# user.net
KiCad netlist of a schematic drawn in Altium Designer
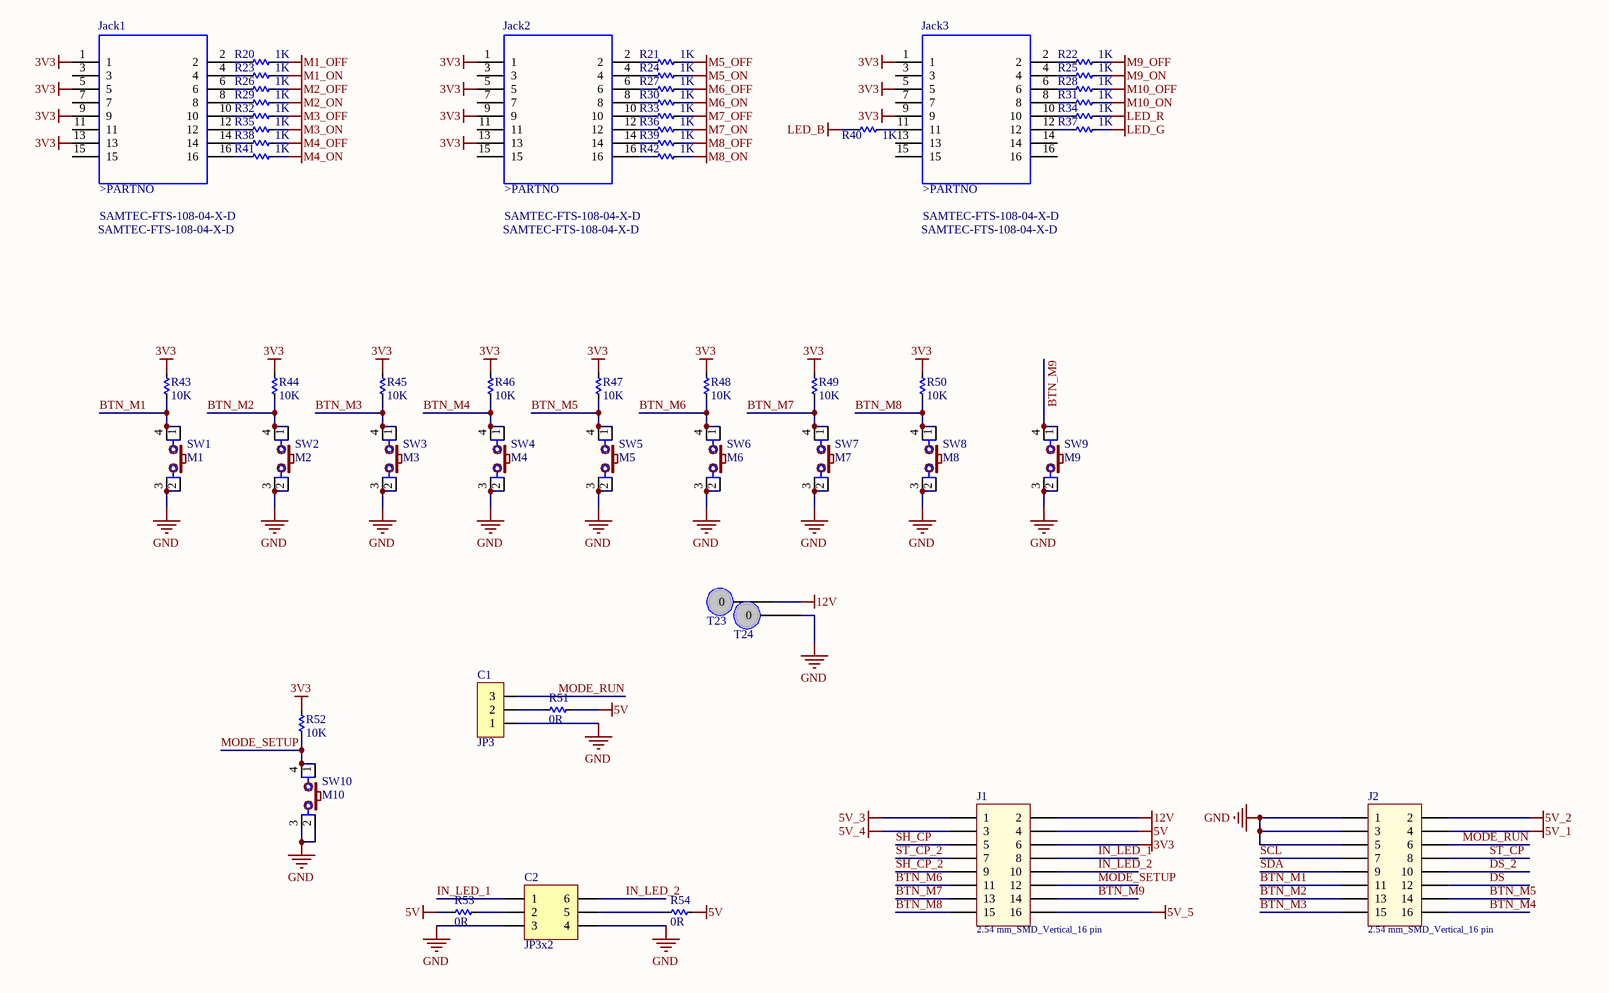
[diagram p0: user.SchDoc]

(export (version "E")
  (design (tool "Eeschema 10.0.6"))
  (components
    (comp (ref "C1")
      (value "JP3")
      (footprint "JP3-D1C")
      (description "WR-PHD 2.54 mm Angled Socket Header")
      (fields
        (field (name "MANUFACTURER") "Würth Elektronik eiSos GmbH")
        (field (name "PARTNO") "613003143121")
        (field (name "CREATED BY") "Karrer Zheng")
      )
      (libsource (lib "LIBRARY") (part "JP3"))
    )
    (comp (ref "C2")
      (value "JP3x2")
      (footprint "JP3-D2C")
      (description "WR-PHD 2.54 mm Dual Socket Header")
      (fields
        (field (name "MANUFACTURER") "Würth Elektronik eiSos GmbH")
        (field (name "PARTNO") "61300621821")
        (field (name "CREATED BY") "Karrer Zheng")
      )
      (libsource (lib "LIBRARY") (part "JP3x2"))
    )
    (comp (ref "J1")
      (value "2.54 mm_SMD_Vertical_16 pin")
      (footprint "61031621121")
      (description "Pin Header WR-PHD, pitch 2.54 mm, SMD, Vertical, dual row, 16 pin")
      (fields (field (name "PART NUMBER") "61031621121") (field (name "PUBLISHER") "Wurth Elektronik"))
      (libsource (lib "Jump2.0") (part "61031621121"))
    )
    (comp (ref "J2")
      (value "2.54 mm_SMD_Vertical_16 pin")
      (footprint "61031621121")
      (description "Pin Header WR-PHD, pitch 2.54 mm, SMD, Vertical, dual row, 16 pin")
      (fields (field (name "PART NUMBER") "61031621121") (field (name "PUBLISHER") "Wurth Elektronik"))
      (libsource (lib "Jump2.0") (part "61031621121"))
    )
    (comp (ref "Jack1")
      (value "SAMTEC-FTS-108-04-X-D")
      (footprint "SAMTEC-FTS-108-04-X-D:SAMTEC-FTS-108-04-X-D")
      (libsource (lib "SAMTEC-FTS-108-04-X-D") (part "SAMTEC-FTS-108-04-X-D"))
    )
    (comp (ref "Jack2")
      (value "SAMTEC-FTS-108-04-X-D")
      (footprint "SAMTEC-FTS-108-04-X-D:SAMTEC-FTS-108-04-X-D")
      (libsource (lib "SAMTEC-FTS-108-04-X-D") (part "SAMTEC-FTS-108-04-X-D"))
    )
    (comp (ref "Jack3")
      (value "SAMTEC-FTS-108-04-X-D")
      (footprint "SAMTEC-FTS-108-04-X-D:SAMTEC-FTS-108-04-X-D")
      (libsource (lib "SAMTEC-FTS-108-04-X-D") (part "SAMTEC-FTS-108-04-X-D"))
    )
    (comp (ref "R20")
      (value "1K")
      (footprint "RES-SMD-0603")
      (description "Resistor")
      (fields
        (field (name "MANUFACTURER") "Generic Components")
        (field (name "PUBLISHER") "Altium Hobart Technology Centre")
      )
      (libsource (lib "LIBRARY") (part "Res-SMD"))
    )
    (comp (ref "R21")
      (value "1K")
      (footprint "RES-SMD-0603")
      (description "Resistor")
      (fields
        (field (name "MANUFACTURER") "Generic Components")
        (field (name "PUBLISHER") "Altium Hobart Technology Centre")
      )
      (libsource (lib "LIBRARY") (part "Res-SMD"))
    )
    (comp (ref "R22")
      (value "1K")
      (footprint "RES-SMD-0603")
      (description "Resistor")
      (fields
        (field (name "MANUFACTURER") "Generic Components")
        (field (name "PUBLISHER") "Altium Hobart Technology Centre")
      )
      (libsource (lib "LIBRARY") (part "Res-SMD"))
    )
    (comp (ref "R23")
      (value "1K")
      (footprint "RES-SMD-0603")
      (description "Resistor")
      (fields
        (field (name "MANUFACTURER") "Generic Components")
        (field (name "PUBLISHER") "Altium Hobart Technology Centre")
      )
      (libsource (lib "LIBRARY") (part "Res-SMD"))
    )
    (comp (ref "R24")
      (value "1K")
      (footprint "RES-SMD-0603")
      (description "Resistor")
      (fields
        (field (name "MANUFACTURER") "Generic Components")
        (field (name "PUBLISHER") "Altium Hobart Technology Centre")
      )
      (libsource (lib "LIBRARY") (part "Res-SMD"))
    )
    (comp (ref "R25")
      (value "1K")
      (footprint "RES-SMD-0603")
      (description "Resistor")
      (fields
        (field (name "MANUFACTURER") "Generic Components")
        (field (name "PUBLISHER") "Altium Hobart Technology Centre")
      )
      (libsource (lib "LIBRARY") (part "Res-SMD"))
    )
    (comp (ref "R26")
      (value "1K")
      (footprint "RES-SMD-0603")
      (description "Resistor")
      (fields
        (field (name "MANUFACTURER") "Generic Components")
        (field (name "PUBLISHER") "Altium Hobart Technology Centre")
      )
      (libsource (lib "LIBRARY") (part "Res-SMD"))
    )
    (comp (ref "R27")
      (value "1K")
      (footprint "RES-SMD-0603")
      (description "Resistor")
      (fields
        (field (name "MANUFACTURER") "Generic Components")
        (field (name "PUBLISHER") "Altium Hobart Technology Centre")
      )
      (libsource (lib "LIBRARY") (part "Res-SMD"))
    )
    (comp (ref "R28")
      (value "1K")
      (footprint "RES-SMD-0603")
      (description "Resistor")
      (fields
        (field (name "MANUFACTURER") "Generic Components")
        (field (name "PUBLISHER") "Altium Hobart Technology Centre")
      )
      (libsource (lib "LIBRARY") (part "Res-SMD"))
    )
    (comp (ref "R29")
      (value "1K")
      (footprint "RES-SMD-0603")
      (description "Resistor")
      (fields
        (field (name "MANUFACTURER") "Generic Components")
        (field (name "PUBLISHER") "Altium Hobart Technology Centre")
      )
      (libsource (lib "LIBRARY") (part "Res-SMD"))
    )
    (comp (ref "R30")
      (value "1K")
      (footprint "RES-SMD-0603")
      (description "Resistor")
      (fields
        (field (name "MANUFACTURER") "Generic Components")
        (field (name "PUBLISHER") "Altium Hobart Technology Centre")
      )
      (libsource (lib "LIBRARY") (part "Res-SMD"))
    )
    (comp (ref "R31")
      (value "1K")
      (footprint "RES-SMD-0603")
      (description "Resistor")
      (fields
        (field (name "MANUFACTURER") "Generic Components")
        (field (name "PUBLISHER") "Altium Hobart Technology Centre")
      )
      (libsource (lib "LIBRARY") (part "Res-SMD"))
    )
    (comp (ref "R32")
      (value "1K")
      (footprint "RES-SMD-0603")
      (description "Resistor")
      (fields
        (field (name "MANUFACTURER") "Generic Components")
        (field (name "PUBLISHER") "Altium Hobart Technology Centre")
      )
      (libsource (lib "LIBRARY") (part "Res-SMD"))
    )
    (comp (ref "R33")
      (value "1K")
      (footprint "RES-SMD-0603")
      (description "Resistor")
      (fields
        (field (name "MANUFACTURER") "Generic Components")
        (field (name "PUBLISHER") "Altium Hobart Technology Centre")
      )
      (libsource (lib "LIBRARY") (part "Res-SMD"))
    )
    (comp (ref "R34")
      (value "1K")
      (footprint "RES-SMD-0603")
      (description "Resistor")
      (fields
        (field (name "MANUFACTURER") "Generic Components")
        (field (name "PUBLISHER") "Altium Hobart Technology Centre")
      )
      (libsource (lib "LIBRARY") (part "Res-SMD"))
    )
    (comp (ref "R35")
      (value "1K")
      (footprint "RES-SMD-0603")
      (description "Resistor")
      (fields
        (field (name "MANUFACTURER") "Generic Components")
        (field (name "PUBLISHER") "Altium Hobart Technology Centre")
      )
      (libsource (lib "LIBRARY") (part "Res-SMD"))
    )
    (comp (ref "R36")
      (value "1K")
      (footprint "RES-SMD-0603")
      (description "Resistor")
      (fields
        (field (name "MANUFACTURER") "Generic Components")
        (field (name "PUBLISHER") "Altium Hobart Technology Centre")
      )
      (libsource (lib "LIBRARY") (part "Res-SMD"))
    )
    (comp (ref "R37")
      (value "1K")
      (footprint "RES-SMD-0603")
      (description "Resistor")
      (fields
        (field (name "MANUFACTURER") "Generic Components")
        (field (name "PUBLISHER") "Altium Hobart Technology Centre")
      )
      (libsource (lib "LIBRARY") (part "Res-SMD"))
    )
    (comp (ref "R38")
      (value "1K")
      (footprint "RES-SMD-0603")
      (description "Resistor")
      (fields
        (field (name "MANUFACTURER") "Generic Components")
        (field (name "PUBLISHER") "Altium Hobart Technology Centre")
      )
      (libsource (lib "LIBRARY") (part "Res-SMD"))
    )
    (comp (ref "R39")
      (value "1K")
      (footprint "RES-SMD-0603")
      (description "Resistor")
      (fields
        (field (name "MANUFACTURER") "Generic Components")
        (field (name "PUBLISHER") "Altium Hobart Technology Centre")
      )
      (libsource (lib "LIBRARY") (part "Res-SMD"))
    )
    (comp (ref "R40")
      (value "1K")
      (footprint "RES-SMD-0603")
      (description "Resistor")
      (fields
        (field (name "MANUFACTURER") "Generic Components")
        (field (name "PUBLISHER") "Altium Hobart Technology Centre")
      )
      (libsource (lib "LIBRARY") (part "Res-SMD"))
    )
    (comp (ref "R41")
      (value "1K")
      (footprint "RES-SMD-0603")
      (description "Resistor")
      (fields
        (field (name "MANUFACTURER") "Generic Components")
        (field (name "PUBLISHER") "Altium Hobart Technology Centre")
      )
      (libsource (lib "LIBRARY") (part "Res-SMD"))
    )
    (comp (ref "R42")
      (value "1K")
      (footprint "RES-SMD-0603")
      (description "Resistor")
      (fields
        (field (name "MANUFACTURER") "Generic Components")
        (field (name "PUBLISHER") "Altium Hobart Technology Centre")
      )
      (libsource (lib "LIBRARY") (part "Res-SMD"))
    )
    (comp (ref "R43")
      (value "10K")
      (footprint "RES-SMD-0603")
      (description "Resistor")
      (fields
        (field (name "MANUFACTURER") "Generic Components")
        (field (name "PUBLISHER") "Altium Hobart Technology Centre")
      )
      (libsource (lib "LIBRARY") (part "Res-SMD"))
    )
    (comp (ref "R44")
      (value "10K")
      (footprint "RES-SMD-0603")
      (description "Resistor")
      (fields
        (field (name "MANUFACTURER") "Generic Components")
        (field (name "PUBLISHER") "Altium Hobart Technology Centre")
      )
      (libsource (lib "LIBRARY") (part "Res-SMD"))
    )
    (comp (ref "R45")
      (value "10K")
      (footprint "RES-SMD-0603")
      (description "Resistor")
      (fields
        (field (name "MANUFACTURER") "Generic Components")
        (field (name "PUBLISHER") "Altium Hobart Technology Centre")
      )
      (libsource (lib "LIBRARY") (part "Res-SMD"))
    )
    (comp (ref "R46")
      (value "10K")
      (footprint "RES-SMD-0603")
      (description "Resistor")
      (fields
        (field (name "MANUFACTURER") "Generic Components")
        (field (name "PUBLISHER") "Altium Hobart Technology Centre")
      )
      (libsource (lib "LIBRARY") (part "Res-SMD"))
    )
    (comp (ref "R47")
      (value "10K")
      (footprint "RES-SMD-0603")
      (description "Resistor")
      (fields
        (field (name "MANUFACTURER") "Generic Components")
        (field (name "PUBLISHER") "Altium Hobart Technology Centre")
      )
      (libsource (lib "LIBRARY") (part "Res-SMD"))
    )
    (comp (ref "R48")
      (value "10K")
      (footprint "RES-SMD-0603")
      (description "Resistor")
      (fields
        (field (name "MANUFACTURER") "Generic Components")
        (field (name "PUBLISHER") "Altium Hobart Technology Centre")
      )
      (libsource (lib "LIBRARY") (part "Res-SMD"))
    )
    (comp (ref "R49")
      (value "10K")
      (footprint "RES-SMD-0603")
      (description "Resistor")
      (fields
        (field (name "MANUFACTURER") "Generic Components")
        (field (name "PUBLISHER") "Altium Hobart Technology Centre")
      )
      (libsource (lib "LIBRARY") (part "Res-SMD"))
    )
    (comp (ref "R50")
      (value "10K")
      (footprint "RES-SMD-0603")
      (description "Resistor")
      (fields
        (field (name "MANUFACTURER") "Generic Components")
        (field (name "PUBLISHER") "Altium Hobart Technology Centre")
      )
      (libsource (lib "LIBRARY") (part "Res-SMD"))
    )
    (comp (ref "R51")
      (value "0R")
      (footprint "RES-SMD-0603")
      (description "Resistor")
      (fields
        (field (name "MANUFACTURER") "Generic Components")
        (field (name "PUBLISHER") "Altium Hobart Technology Centre")
      )
      (libsource (lib "LIBRARY") (part "Res-SMD"))
    )
    (comp (ref "R52")
      (value "10K")
      (footprint "RES-SMD-0603")
      (description "Resistor")
      (fields
        (field (name "MANUFACTURER") "Generic Components")
        (field (name "PUBLISHER") "Altium Hobart Technology Centre")
      )
      (libsource (lib "LIBRARY") (part "Res-SMD"))
    )
    (comp (ref "R53")
      (value "0R")
      (footprint "RES-SMD-0603")
      (description "Resistor")
      (fields
        (field (name "MANUFACTURER") "Generic Components")
        (field (name "PUBLISHER") "Altium Hobart Technology Centre")
      )
      (libsource (lib "LIBRARY") (part "Res-SMD"))
    )
    (comp (ref "R54")
      (value "0R")
      (footprint "RES-SMD-0603")
      (description "Resistor")
      (fields
        (field (name "MANUFACTURER") "Generic Components")
        (field (name "PUBLISHER") "Altium Hobart Technology Centre")
      )
      (libsource (lib "LIBRARY") (part "Res-SMD"))
    )
    (comp (ref "SW1")
      (value "M1")
      (footprint "SW2-SMD")
      (description "Switch button 4 pin")
      (libsource (lib "LIBTanCN") (part "SW4"))
    )
    (comp (ref "SW2")
      (value "M2")
      (footprint "SW2-SMD")
      (description "Switch button 4 pin")
      (libsource (lib "LIBTanCN") (part "SW4"))
    )
    (comp (ref "SW3")
      (value "M3")
      (footprint "SW2-SMD")
      (description "Switch button 4 pin")
      (libsource (lib "LIBTanCN") (part "SW4"))
    )
    (comp (ref "SW4")
      (value "M4")
      (footprint "SW2-SMD")
      (description "Switch button 4 pin")
      (libsource (lib "LIBTanCN") (part "SW4"))
    )
    (comp (ref "SW5")
      (value "M5")
      (footprint "SW2-SMD")
      (description "Switch button 4 pin")
      (libsource (lib "LIBTanCN") (part "SW4"))
    )
    (comp (ref "SW6")
      (value "M6")
      (footprint "SW2-SMD")
      (description "Switch button 4 pin")
      (libsource (lib "LIBTanCN") (part "SW4"))
    )
    (comp (ref "SW7")
      (value "M7")
      (footprint "SW2-SMD")
      (description "Switch button 4 pin")
      (libsource (lib "LIBTanCN") (part "SW4"))
    )
    (comp (ref "SW8")
      (value "M8")
      (footprint "SW2-SMD")
      (description "Switch button 4 pin")
      (libsource (lib "LIBTanCN") (part "SW4"))
    )
    (comp (ref "SW9")
      (value "M9")
      (footprint "SW2-SMD")
      (description "Switch button 4 pin")
      (libsource (lib "LIBTanCN") (part "SW4"))
    )
    (comp (ref "SW10")
      (value "M10")
      (footprint "SW2-SMD")
      (description "Switch button 4 pin")
      (libsource (lib "LIBTanCN") (part "SW4"))
    )
    (comp (ref "T23")
      (value "Pad")
      (footprint "pad_ina:PCBComponent_1")
      (description "pad")
      (libsource (lib "pad_ina") (part "Component_1"))
    )
    (comp (ref "T24")
      (value "Pad")
      (footprint "pad_ina:PCBComponent_1")
      (description "pad")
      (libsource (lib "pad_ina") (part "Component_1"))
    )
  )
  (nets
    (net (code "1") (name "/BTN_M1") (class "Default")
      (node (ref "J2") (pin "11") (pinfunction "11_11") (pintype "passive"))
      (node (ref "R43") (pin "2") (pinfunction "2_2") (pintype "passive"))
      (node (ref "SW1") (pin "1") (pintype "passive"))
      (node (ref "SW1") (pin "4") (pinfunction "4_4") (pintype "passive"))
    )
    (net (code "2") (name "/BTN_M2") (class "Default")
      (node (ref "J2") (pin "13") (pinfunction "13_13") (pintype "passive"))
      (node (ref "R44") (pin "2") (pinfunction "2_2") (pintype "passive"))
      (node (ref "SW2") (pin "1") (pintype "passive"))
      (node (ref "SW2") (pin "4") (pinfunction "4_4") (pintype "passive"))
    )
    (net (code "3") (name "/BTN_M3") (class "Default")
      (node (ref "J2") (pin "15") (pinfunction "15_15") (pintype "passive"))
      (node (ref "R45") (pin "2") (pinfunction "2_2") (pintype "passive"))
      (node (ref "SW3") (pin "1") (pintype "passive"))
      (node (ref "SW3") (pin "4") (pinfunction "4_4") (pintype "passive"))
    )
    (net (code "4") (name "/BTN_M4") (class "Default")
      (node (ref "J2") (pin "16") (pinfunction "16_16") (pintype "passive"))
      (node (ref "R46") (pin "2") (pinfunction "2_2") (pintype "passive"))
      (node (ref "SW4") (pin "1") (pintype "passive"))
      (node (ref "SW4") (pin "4") (pinfunction "4_4") (pintype "passive"))
    )
    (net (code "5") (name "/BTN_M5") (class "Default")
      (node (ref "J2") (pin "14") (pinfunction "14_14") (pintype "passive"))
      (node (ref "R47") (pin "2") (pinfunction "2_2") (pintype "passive"))
      (node (ref "SW5") (pin "1") (pintype "passive"))
      (node (ref "SW5") (pin "4") (pinfunction "4_4") (pintype "passive"))
    )
    (net (code "6") (name "/BTN_M6") (class "Default")
      (node (ref "J1") (pin "11") (pinfunction "11_11") (pintype "passive"))
      (node (ref "R48") (pin "2") (pinfunction "2_2") (pintype "passive"))
      (node (ref "SW6") (pin "1") (pintype "passive"))
      (node (ref "SW6") (pin "4") (pinfunction "4_4") (pintype "passive"))
    )
    (net (code "7") (name "/BTN_M7") (class "Default")
      (node (ref "J1") (pin "13") (pinfunction "13_13") (pintype "passive"))
      (node (ref "R49") (pin "2") (pinfunction "2_2") (pintype "passive"))
      (node (ref "SW7") (pin "1") (pintype "passive"))
      (node (ref "SW7") (pin "4") (pinfunction "4_4") (pintype "passive"))
    )
    (net (code "8") (name "/BTN_M8") (class "Default")
      (node (ref "J1") (pin "15") (pinfunction "15_15") (pintype "passive"))
      (node (ref "R50") (pin "2") (pinfunction "2_2") (pintype "passive"))
      (node (ref "SW8") (pin "1") (pintype "passive"))
      (node (ref "SW8") (pin "4") (pinfunction "4_4") (pintype "passive"))
    )
    (net (code "9") (name "/BTN_M9") (class "Default")
      (node (ref "J1") (pin "14") (pinfunction "14_14") (pintype "passive"))
      (node (ref "SW9") (pin "1") (pintype "passive"))
      (node (ref "SW9") (pin "4") (pinfunction "4_4") (pintype "passive"))
    )
    (net (code "10") (name "/DS") (class "Default")
      (node (ref "J2") (pin "12") (pinfunction "12_12") (pintype "passive"))
    )
    (net (code "11") (name "/DS_2") (class "Default")
      (node (ref "J2") (pin "10") (pinfunction "10_10") (pintype "passive"))
    )
    (net (code "12") (name "/IN_LED_1") (class "Default")
      (node (ref "C2") (pin "1") (pinfunction "1_1") (pintype "passive"))
      (node (ref "J1") (pin "8") (pinfunction "8_8") (pintype "passive"))
    )
    (net (code "13") (name "/IN_LED_2") (class "Default")
      (node (ref "C2") (pin "6") (pinfunction "6_6") (pintype "passive"))
      (node (ref "J1") (pin "10") (pinfunction "10_10") (pintype "passive"))
    )
    (net (code "14") (name "/MODE_RUN") (class "Default")
      (node (ref "C1") (pin "3") (pinfunction "3_3") (pintype "passive"))
      (node (ref "J2") (pin "6") (pinfunction "6_6") (pintype "passive"))
    )
    (net (code "15") (name "/MODE_SETUP") (class "Default")
      (node (ref "J1") (pin "12") (pinfunction "12_12") (pintype "passive"))
      (node (ref "R52") (pin "2") (pinfunction "2_2") (pintype "passive"))
      (node (ref "SW10") (pin "1") (pintype "passive"))
      (node (ref "SW10") (pin "4") (pinfunction "4_4") (pintype "passive"))
    )
    (net (code "16") (name "/SCL") (class "Default")
      (node (ref "J2") (pin "7") (pinfunction "7_7") (pintype "passive"))
    )
    (net (code "17") (name "/SDA") (class "Default")
      (node (ref "J2") (pin "9") (pinfunction "9_9") (pintype "passive"))
    )
    (net (code "18") (name "/SH_CP") (class "Default")
      (node (ref "J1") (pin "5") (pinfunction "5_5") (pintype "passive"))
    )
    (net (code "19") (name "/SH_CP_2") (class "Default")
      (node (ref "J1") (pin "9") (pinfunction "9_9") (pintype "passive"))
    )
    (net (code "20") (name "/ST_CP") (class "Default")
      (node (ref "J2") (pin "8") (pinfunction "8_8") (pintype "passive"))
    )
    (net (code "21") (name "/ST_CP_2") (class "Default")
      (node (ref "J1") (pin "7") (pinfunction "7_7") (pintype "passive"))
    )
    (net (code "22") (name "3V3") (class "Default")
      (node (ref "J1") (pin "6") (pinfunction "6_6") (pintype "passive"))
      (node (ref "Jack1") (pin "1") (pinfunction "1_1") (pintype "passive"))
      (node (ref "Jack1") (pin "13") (pinfunction "13_13") (pintype "passive"))
      (node (ref "Jack1") (pin "5") (pinfunction "5_5") (pintype "passive"))
      (node (ref "Jack1") (pin "9") (pinfunction "9_9") (pintype "passive"))
      (node (ref "Jack2") (pin "1") (pinfunction "1_1") (pintype "passive"))
      (node (ref "Jack2") (pin "13") (pinfunction "13_13") (pintype "passive"))
      (node (ref "Jack2") (pin "5") (pinfunction "5_5") (pintype "passive"))
      (node (ref "Jack2") (pin "9") (pinfunction "9_9") (pintype "passive"))
      (node (ref "Jack3") (pin "1") (pinfunction "1_1") (pintype "passive"))
      (node (ref "Jack3") (pin "5") (pinfunction "5_5") (pintype "passive"))
      (node (ref "Jack3") (pin "9") (pinfunction "9_9") (pintype "passive"))
      (node (ref "R43") (pin "1") (pinfunction "1_1") (pintype "passive"))
      (node (ref "R44") (pin "1") (pinfunction "1_1") (pintype "passive"))
      (node (ref "R45") (pin "1") (pinfunction "1_1") (pintype "passive"))
      (node (ref "R46") (pin "1") (pinfunction "1_1") (pintype "passive"))
      (node (ref "R47") (pin "1") (pinfunction "1_1") (pintype "passive"))
      (node (ref "R48") (pin "1") (pinfunction "1_1") (pintype "passive"))
      (node (ref "R49") (pin "1") (pinfunction "1_1") (pintype "passive"))
      (node (ref "R50") (pin "1") (pinfunction "1_1") (pintype "passive"))
      (node (ref "R52") (pin "1") (pinfunction "1_1") (pintype "passive"))
    )
    (net (code "23") (name "5V") (class "Default")
      (node (ref "J1") (pin "4") (pinfunction "4_4") (pintype "passive"))
      (node (ref "R51") (pin "1") (pinfunction "1_1") (pintype "passive"))
      (node (ref "R53") (pin "2") (pinfunction "2_2") (pintype "passive"))
      (node (ref "R54") (pin "1") (pinfunction "1_1") (pintype "passive"))
    )
    (net (code "24") (name "5V_1") (class "Default")
      (node (ref "J2") (pin "4") (pinfunction "4_4") (pintype "passive"))
    )
    (net (code "25") (name "5V_2") (class "Default")
      (node (ref "J2") (pin "2") (pinfunction "2_2") (pintype "passive"))
    )
    (net (code "26") (name "5V_3") (class "Default")
      (node (ref "J1") (pin "1") (pinfunction "1_1") (pintype "passive"))
    )
    (net (code "27") (name "5V_4") (class "Default")
      (node (ref "J1") (pin "3") (pinfunction "3_3") (pintype "passive"))
    )
    (net (code "28") (name "5V_5") (class "Default")
      (node (ref "J1") (pin "16") (pinfunction "16_16") (pintype "passive"))
    )
    (net (code "29") (name "12V") (class "Default")
      (node (ref "J1") (pin "2") (pinfunction "2_2") (pintype "passive"))
      (node (ref "T23") (pin "0") (pinfunction "0_0") (pintype "passive"))
    )
    (net (code "30") (name "GND") (class "Default")
      (node (ref "C1") (pin "1") (pinfunction "1_1") (pintype "passive"))
      (node (ref "C2") (pin "3") (pinfunction "3_3") (pintype "passive"))
      (node (ref "C2") (pin "4") (pinfunction "4_4") (pintype "passive"))
      (node (ref "J2") (pin "1") (pinfunction "1_1") (pintype "passive"))
      (node (ref "J2") (pin "3") (pinfunction "3_3") (pintype "passive"))
      (node (ref "J2") (pin "5") (pinfunction "5_5") (pintype "passive"))
      (node (ref "SW1") (pin "2") (pinfunction "2_2") (pintype "passive"))
      (node (ref "SW1") (pin "3") (pinfunction "3_3") (pintype "passive"))
      (node (ref "SW10") (pin "2") (pinfunction "2_2") (pintype "passive"))
      (node (ref "SW10") (pin "3") (pinfunction "3_3") (pintype "passive"))
      (node (ref "SW2") (pin "2") (pinfunction "2_2") (pintype "passive"))
      (node (ref "SW2") (pin "3") (pinfunction "3_3") (pintype "passive"))
      (node (ref "SW3") (pin "2") (pinfunction "2_2") (pintype "passive"))
      (node (ref "SW3") (pin "3") (pinfunction "3_3") (pintype "passive"))
      (node (ref "SW4") (pin "2") (pinfunction "2_2") (pintype "passive"))
      (node (ref "SW4") (pin "3") (pinfunction "3_3") (pintype "passive"))
      (node (ref "SW5") (pin "2") (pinfunction "2_2") (pintype "passive"))
      (node (ref "SW5") (pin "3") (pinfunction "3_3") (pintype "passive"))
      (node (ref "SW6") (pin "2") (pinfunction "2_2") (pintype "passive"))
      (node (ref "SW6") (pin "3") (pinfunction "3_3") (pintype "passive"))
      (node (ref "SW7") (pin "2") (pinfunction "2_2") (pintype "passive"))
      (node (ref "SW7") (pin "3") (pinfunction "3_3") (pintype "passive"))
      (node (ref "SW8") (pin "2") (pinfunction "2_2") (pintype "passive"))
      (node (ref "SW8") (pin "3") (pinfunction "3_3") (pintype "passive"))
      (node (ref "SW9") (pin "2") (pinfunction "2_2") (pintype "passive"))
      (node (ref "SW9") (pin "3") (pinfunction "3_3") (pintype "passive"))
      (node (ref "T24") (pin "0") (pinfunction "0_0") (pintype "passive"))
    )
    (net (code "31") (name "LED_B") (class "Default")
      (node (ref "R40") (pin "2") (pinfunction "2_2") (pintype "passive"))
    )
    (net (code "32") (name "LED_G") (class "Default")
      (node (ref "R37") (pin "2") (pinfunction "2_2") (pintype "passive"))
    )
    (net (code "33") (name "LED_R") (class "Default")
      (node (ref "R34") (pin "2") (pinfunction "2_2") (pintype "passive"))
    )
    (net (code "34") (name "M1_OFF") (class "Default")
      (node (ref "R20") (pin "2") (pinfunction "2_2") (pintype "passive"))
    )
    (net (code "35") (name "M1_ON") (class "Default")
      (node (ref "R23") (pin "2") (pinfunction "2_2") (pintype "passive"))
    )
    (net (code "36") (name "M2_OFF") (class "Default")
      (node (ref "R26") (pin "2") (pinfunction "2_2") (pintype "passive"))
    )
    (net (code "37") (name "M2_ON") (class "Default")
      (node (ref "R29") (pin "2") (pinfunction "2_2") (pintype "passive"))
    )
    (net (code "38") (name "M3_OFF") (class "Default")
      (node (ref "R32") (pin "2") (pinfunction "2_2") (pintype "passive"))
    )
    (net (code "39") (name "M3_ON") (class "Default")
      (node (ref "R35") (pin "2") (pinfunction "2_2") (pintype "passive"))
    )
    (net (code "40") (name "M4_OFF") (class "Default")
      (node (ref "R38") (pin "2") (pinfunction "2_2") (pintype "passive"))
    )
    (net (code "41") (name "M4_ON") (class "Default")
      (node (ref "R41") (pin "2") (pinfunction "2_2") (pintype "passive"))
    )
    (net (code "42") (name "M5_OFF") (class "Default")
      (node (ref "R21") (pin "2") (pinfunction "2_2") (pintype "passive"))
    )
    (net (code "43") (name "M5_ON") (class "Default")
      (node (ref "R24") (pin "2") (pinfunction "2_2") (pintype "passive"))
    )
    (net (code "44") (name "M6_OFF") (class "Default")
      (node (ref "R27") (pin "2") (pinfunction "2_2") (pintype "passive"))
    )
    (net (code "45") (name "M6_ON") (class "Default")
      (node (ref "R30") (pin "2") (pinfunction "2_2") (pintype "passive"))
    )
    (net (code "46") (name "M7_OFF") (class "Default")
      (node (ref "R33") (pin "2") (pinfunction "2_2") (pintype "passive"))
    )
    (net (code "47") (name "M7_ON") (class "Default")
      (node (ref "R36") (pin "2") (pinfunction "2_2") (pintype "passive"))
    )
    (net (code "48") (name "M8_OFF") (class "Default")
      (node (ref "R39") (pin "2") (pinfunction "2_2") (pintype "passive"))
    )
    (net (code "49") (name "M8_ON") (class "Default")
      (node (ref "R42") (pin "2") (pinfunction "2_2") (pintype "passive"))
    )
    (net (code "50") (name "M9_OFF") (class "Default")
      (node (ref "R22") (pin "2") (pinfunction "2_2") (pintype "passive"))
    )
    (net (code "51") (name "M9_ON") (class "Default")
      (node (ref "R25") (pin "2") (pinfunction "2_2") (pintype "passive"))
    )
    (net (code "52") (name "M10_OFF") (class "Default")
      (node (ref "R28") (pin "2") (pinfunction "2_2") (pintype "passive"))
    )
    (net (code "53") (name "M10_ON") (class "Default")
      (node (ref "R31") (pin "2") (pinfunction "2_2") (pintype "passive"))
    )
    (net (code "54") (name "Net-(C1-Pad2)") (class "Default")
      (node (ref "C1") (pin "2") (pinfunction "2_2") (pintype "passive"))
      (node (ref "R51") (pin "2") (pinfunction "2_2") (pintype "passive"))
    )
    (net (code "55") (name "Net-(C2-Pad2)") (class "Default")
      (node (ref "C2") (pin "2") (pinfunction "2_2") (pintype "passive"))
      (node (ref "R53") (pin "1") (pinfunction "1_1") (pintype "passive"))
    )
    (net (code "56") (name "Net-(C2-Pad5)") (class "Default")
      (node (ref "C2") (pin "5") (pinfunction "5_5") (pintype "passive"))
      (node (ref "R54") (pin "2") (pinfunction "2_2") (pintype "passive"))
    )
    (net (code "57") (name "Net-(Jack1-Pad2)") (class "Default")
      (node (ref "Jack1") (pin "2") (pinfunction "2_2") (pintype "passive"))
      (node (ref "R20") (pin "1") (pinfunction "1_1") (pintype "passive"))
    )
    (net (code "58") (name "Net-(Jack1-Pad4)") (class "Default")
      (node (ref "Jack1") (pin "4") (pinfunction "4_4") (pintype "passive"))
      (node (ref "R23") (pin "1") (pinfunction "1_1") (pintype "passive"))
    )
    (net (code "59") (name "Net-(Jack1-Pad6)") (class "Default")
      (node (ref "Jack1") (pin "6") (pinfunction "6_6") (pintype "passive"))
      (node (ref "R26") (pin "1") (pinfunction "1_1") (pintype "passive"))
    )
    (net (code "60") (name "Net-(Jack1-Pad8)") (class "Default")
      (node (ref "Jack1") (pin "8") (pinfunction "8_8") (pintype "passive"))
      (node (ref "R29") (pin "1") (pinfunction "1_1") (pintype "passive"))
    )
    (net (code "61") (name "Net-(Jack1-Pad10)") (class "Default")
      (node (ref "Jack1") (pin "10") (pinfunction "10_10") (pintype "passive"))
      (node (ref "R32") (pin "1") (pinfunction "1_1") (pintype "passive"))
    )
    (net (code "62") (name "Net-(Jack1-Pad12)") (class "Default")
      (node (ref "Jack1") (pin "12") (pinfunction "12_12") (pintype "passive"))
      (node (ref "R35") (pin "1") (pinfunction "1_1") (pintype "passive"))
    )
    (net (code "63") (name "Net-(Jack1-Pad14)") (class "Default")
      (node (ref "Jack1") (pin "14") (pinfunction "14_14") (pintype "passive"))
      (node (ref "R38") (pin "1") (pinfunction "1_1") (pintype "passive"))
    )
    (net (code "64") (name "Net-(Jack1-Pad16)") (class "Default")
      (node (ref "Jack1") (pin "16") (pinfunction "16_16") (pintype "passive"))
      (node (ref "R41") (pin "1") (pinfunction "1_1") (pintype "passive"))
    )
    (net (code "65") (name "Net-(Jack2-Pad2)") (class "Default")
      (node (ref "Jack2") (pin "2") (pinfunction "2_2") (pintype "passive"))
      (node (ref "R21") (pin "1") (pinfunction "1_1") (pintype "passive"))
    )
    (net (code "66") (name "Net-(Jack2-Pad4)") (class "Default")
      (node (ref "Jack2") (pin "4") (pinfunction "4_4") (pintype "passive"))
      (node (ref "R24") (pin "1") (pinfunction "1_1") (pintype "passive"))
    )
    (net (code "67") (name "Net-(Jack2-Pad6)") (class "Default")
      (node (ref "Jack2") (pin "6") (pinfunction "6_6") (pintype "passive"))
      (node (ref "R27") (pin "1") (pinfunction "1_1") (pintype "passive"))
    )
    (net (code "68") (name "Net-(Jack2-Pad8)") (class "Default")
      (node (ref "Jack2") (pin "8") (pinfunction "8_8") (pintype "passive"))
      (node (ref "R30") (pin "1") (pinfunction "1_1") (pintype "passive"))
    )
    (net (code "69") (name "Net-(Jack2-Pad10)") (class "Default")
      (node (ref "Jack2") (pin "10") (pinfunction "10_10") (pintype "passive"))
      (node (ref "R33") (pin "1") (pinfunction "1_1") (pintype "passive"))
    )
    (net (code "70") (name "Net-(Jack2-Pad12)") (class "Default")
      (node (ref "Jack2") (pin "12") (pinfunction "12_12") (pintype "passive"))
      (node (ref "R36") (pin "1") (pinfunction "1_1") (pintype "passive"))
    )
    (net (code "71") (name "Net-(Jack2-Pad14)") (class "Default")
      (node (ref "Jack2") (pin "14") (pinfunction "14_14") (pintype "passive"))
      (node (ref "R39") (pin "1") (pinfunction "1_1") (pintype "passive"))
    )
    (net (code "72") (name "Net-(Jack2-Pad16)") (class "Default")
      (node (ref "Jack2") (pin "16") (pinfunction "16_16") (pintype "passive"))
      (node (ref "R42") (pin "1") (pinfunction "1_1") (pintype "passive"))
    )
    (net (code "73") (name "Net-(Jack3-Pad2)") (class "Default")
      (node (ref "Jack3") (pin "2") (pinfunction "2_2") (pintype "passive"))
      (node (ref "R22") (pin "1") (pinfunction "1_1") (pintype "passive"))
    )
    (net (code "74") (name "Net-(Jack3-Pad4)") (class "Default")
      (node (ref "Jack3") (pin "4") (pinfunction "4_4") (pintype "passive"))
      (node (ref "R25") (pin "1") (pinfunction "1_1") (pintype "passive"))
    )
    (net (code "75") (name "Net-(Jack3-Pad6)") (class "Default")
      (node (ref "Jack3") (pin "6") (pinfunction "6_6") (pintype "passive"))
      (node (ref "R28") (pin "1") (pinfunction "1_1") (pintype "passive"))
    )
    (net (code "76") (name "Net-(Jack3-Pad8)") (class "Default")
      (node (ref "Jack3") (pin "8") (pinfunction "8_8") (pintype "passive"))
      (node (ref "R31") (pin "1") (pinfunction "1_1") (pintype "passive"))
    )
    (net (code "77") (name "Net-(Jack3-Pad10)") (class "Default")
      (node (ref "Jack3") (pin "10") (pinfunction "10_10") (pintype "passive"))
      (node (ref "R34") (pin "1") (pinfunction "1_1") (pintype "passive"))
    )
    (net (code "78") (name "Net-(Jack3-Pad11)") (class "Default")
      (node (ref "Jack3") (pin "11") (pinfunction "11_11") (pintype "passive"))
      (node (ref "R40") (pin "1") (pinfunction "1_1") (pintype "passive"))
    )
    (net (code "79") (name "Net-(Jack3-Pad12)") (class "Default")
      (node (ref "Jack3") (pin "12") (pinfunction "12_12") (pintype "passive"))
      (node (ref "R37") (pin "1") (pinfunction "1_1") (pintype "passive"))
    )
    (net (code "80") (name "unconnected-(Jack1-Pad3)") (class "Default")
      (node (ref "Jack1") (pin "3") (pinfunction "3_3") (pintype "passive"))
    )
    (net (code "81") (name "unconnected-(Jack1-Pad7)") (class "Default")
      (node (ref "Jack1") (pin "7") (pinfunction "7_7") (pintype "passive"))
    )
    (net (code "82") (name "unconnected-(Jack1-Pad11)") (class "Default")
      (node (ref "Jack1") (pin "11") (pinfunction "11_11") (pintype "passive"))
    )
    (net (code "83") (name "unconnected-(Jack1-Pad15)") (class "Default")
      (node (ref "Jack1") (pin "15") (pinfunction "15_15") (pintype "passive"))
    )
    (net (code "84") (name "unconnected-(Jack2-Pad3)") (class "Default")
      (node (ref "Jack2") (pin "3") (pinfunction "3_3") (pintype "passive"))
    )
    (net (code "85") (name "unconnected-(Jack2-Pad7)") (class "Default")
      (node (ref "Jack2") (pin "7") (pinfunction "7_7") (pintype "passive"))
    )
    (net (code "86") (name "unconnected-(Jack2-Pad11)") (class "Default")
      (node (ref "Jack2") (pin "11") (pinfunction "11_11") (pintype "passive"))
    )
    (net (code "87") (name "unconnected-(Jack2-Pad15)") (class "Default")
      (node (ref "Jack2") (pin "15") (pinfunction "15_15") (pintype "passive"))
    )
    (net (code "88") (name "unconnected-(Jack3-Pad3)") (class "Default")
      (node (ref "Jack3") (pin "3") (pinfunction "3_3") (pintype "passive"))
    )
    (net (code "89") (name "unconnected-(Jack3-Pad7)") (class "Default")
      (node (ref "Jack3") (pin "7") (pinfunction "7_7") (pintype "passive"))
    )
    (net (code "90") (name "unconnected-(Jack3-Pad13)") (class "Default")
      (node (ref "Jack3") (pin "13") (pinfunction "13_13") (pintype "passive"))
    )
    (net (code "91") (name "unconnected-(Jack3-Pad14)") (class "Default")
      (node (ref "Jack3") (pin "14") (pinfunction "14_14") (pintype "passive"))
    )
    (net (code "92") (name "unconnected-(Jack3-Pad15)") (class "Default")
      (node (ref "Jack3") (pin "15") (pinfunction "15_15") (pintype "passive"))
    )
    (net (code "93") (name "unconnected-(Jack3-Pad16)") (class "Default")
      (node (ref "Jack3") (pin "16") (pinfunction "16_16") (pintype "passive"))
    )
  )
)
